# VoltageRegulator.net
KiCad netlist of a schematic drawn in Altium Designer
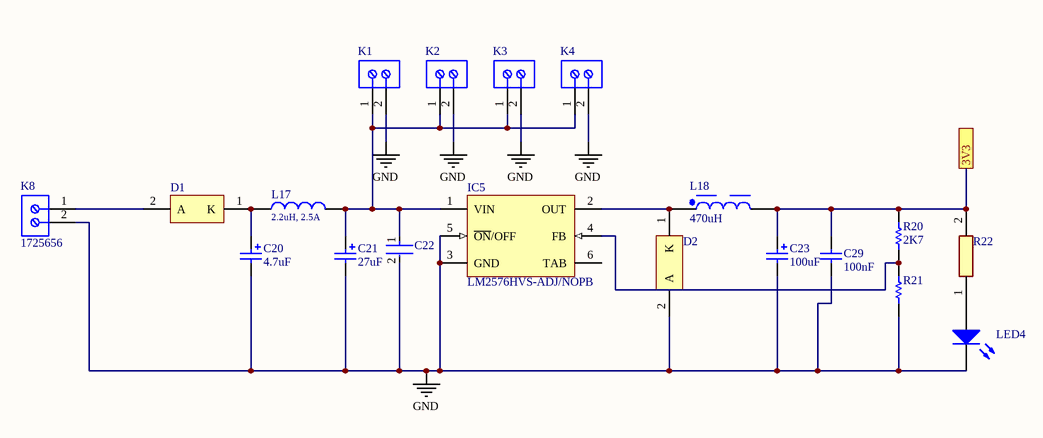
[diagram p0: VoltageRegulator.SchDoc]

(export (version "E")
  (design (tool "Eeschema 10.0.6"))
  (components
    (comp (ref "C20")
      (value "4.7uF")
      (footprint "WCAP-PSLP_D6.3H7.7")
      (description "WCAP-PSLP Aluminum Polymer Capacitor, V-Chip, SMT, D6.3xH7.7mm, 4.7uF, 100V")
      (fields
        (field (name "MANUFACTURER PART NUMBER") "875105945001")
        (field (name "MANUFACTURER") "Wurth Elektronik")
      )
      (libsource (lib "Altium_WCAP-PSLP (rev20b)") (part "875105945001"))
    )
    (comp (ref "C21")
      (value "27uF")
      (footprint "WCAP-ATUL_D8H11.5")
      (description "WCAP-ATUL Aluminum Electrolytic Capacitor, Radial, THT, D8xH11.5mm, 27uF, 100V")
      (fields
        (field (name "MANUFACTURER") "Wurth Elektronik")
        (field (name "MANUFACTURER PART NUMBER") "860040874001")
      )
      (libsource (lib "Altium_WCAP-ATUL (rev20b)") (part "860040874001"))
    )
    (comp (ref "C22")
      (value "~")
      (footprint "FP-GRM32-MFG")
      (description "CAP CER 4.7UF 50V X7R 1210")
      (fields (field (name "MANUFACTURER") "Murata") (field (name "TOLERANCE") "10%"))
      (libsource (lib "Altium Content Vault") (part "b4654b650e69147ec39a6b967a45e02"))
    )
    (comp (ref "C23")
      (value "100uF")
      (footprint "WCAP-PSLP_D5H5.5")
      (description "WCAP-PSLP Aluminum Polymer Capacitor, V-Chip, SMT, D5xH5.5mm, 100uF, 10V")
      (fields
        (field (name "MANUFACTURER PART NUMBER") "875105242010")
        (field (name "MANUFACTURER") "Wurth Elektronik")
      )
      (libsource (lib "Altium_WCAP-PSLP (rev20b)") (part "875105242010"))
    )
    (comp (ref "C29")
      (value "100nF")
      (footprint "WCAP-CSGP_0805_H=1.25mm")
      (description "WCAP-CSGP Multilayer Ceramic Chip Capacitor, General Purpose, size 0805, X7R, 100nF, 100V")
      (fields
        (field (name "MANUFACTURER PART NUMBER") "885012207128")
        (field (name "MANUFACTURER") "Wurth Elektronik")
      )
      (libsource (lib "Altium_WCAP-CSGP (rev21a)") (part "885012207128"))
    )
    (comp (ref "D1")
      (value "~")
      (footprint "ONSC-SMC-2-403-03_V")
      (description "Schottky Power Rectifier, 2-Pin SMC, Pb-Free, Tape and Reel")
      (fields (field (name "MANUFACTURER") "On Semiconductor") (field (name "PARTNUMBER") "MBRS540T3G"))
      (libsource (lib "Altium Content Vault") (part "ONSC-D-K1A2-2_A"))
    )
    (comp (ref "D2")
      (value "~")
      (footprint "ONSC-SMC-2-403-03_V")
      (description "Schottky Power Rectifier, 2-Pin SMC, Pb-Free, Tape and Reel")
      (fields (field (name "MANUFACTURER") "On Semiconductor") (field (name "PARTNUMBER") "MBRS540T3G"))
      (libsource (lib "") (part "ONSC-D-K1A2-2_A_1"))
    )
    (comp (ref "IC5")
      (value "LM2576HVS-ADJ/NOPB")
      (footprint "KTT0005B_N")
      (description "SIMPLE SWITCHER® 3A Step-Down Voltage Regulator, 5-pin TO-263, Pb-Free")
      (fields (field (name "MANUFACTURER") "Texas Instruments"))
      (libsource (lib "Altium Content Vault") (part "PM-REG-LM2575HVS-12"))
    )
    (comp (ref "K1")
      (value "~")
      (footprint "PHOE-1725656-2")
      (description "Male Header, Pitch 2.54 mm, 1 x 2 Position, Height 9 mm, Tail Length 3.5 mm")
      (fields
        (field (name "MANUFACTURER PART NO.") "1725656")
        (field (name "MANUFACTURER") "Phoenix Contact")
      )
      (libsource (lib "Altium Content Vault") (part "CN-1P-F-TB2"))
    )
    (comp (ref "K2")
      (value "~")
      (footprint "PHOE-1725656-2")
      (description "Male Header, Pitch 2.54 mm, 1 x 2 Position, Height 9 mm, Tail Length 3.5 mm")
      (fields
        (field (name "MANUFACTURER PART NO.") "1725656")
        (field (name "MANUFACTURER") "Phoenix Contact")
      )
      (libsource (lib "Altium Content Vault") (part "CN-1P-F-TB2"))
    )
    (comp (ref "K3")
      (value "~")
      (footprint "PHOE-1725656-2")
      (description "Male Header, Pitch 2.54 mm, 1 x 2 Position, Height 9 mm, Tail Length 3.5 mm")
      (fields
        (field (name "MANUFACTURER PART NO.") "1725656")
        (field (name "MANUFACTURER") "Phoenix Contact")
      )
      (libsource (lib "Altium Content Vault") (part "CN-1P-F-TB2"))
    )
    (comp (ref "K4")
      (value "~")
      (footprint "PHOE-1725656-2")
      (description "Male Header, Pitch 2.54 mm, 1 x 2 Position, Height 9 mm, Tail Length 3.5 mm")
      (fields
        (field (name "MANUFACTURER PART NO.") "1725656")
        (field (name "MANUFACTURER") "Phoenix Contact")
      )
      (libsource (lib "Altium Content Vault") (part "CN-1P-F-TB2"))
    )
    (comp (ref "K8")
      (value "1725656")
      (footprint "PHOE-1725656-2")
      (description "Male Header, Pitch 2.54 mm, 1 x 2 Position, Height 9 mm, Tail Length 3.5 mm")
      (fields (field (name "MANUFACTURER") "Phoenix Contact"))
      (libsource (lib "Altium Content Vault") (part "CN-1P-F-TB2"))
    )
    (comp (ref "L17")
      (value "2.2uH, 2.5A")
      (footprint "WE-PD2_4532")
      (description "WE-PD2 SMT Power Inductor, size 4532, 2.2uH, 2.5A")
      (fields
        (field (name "MANUFACTURER") "Wurth Elektronik")
        (field (name "MANUFACTURER PART NUMBER") "744773022")
      )
      (libsource (lib "WE-PD2 (rev20a)") (part "744773022"))
    )
    (comp (ref "L18")
      (value "470uH")
      (footprint "WE-PD_1050P")
      (description "WE-PD SMT Power Inductor, size 1050P, 470uH, 0.6A, 960mOhm")
      (fields
        (field (name "MANUFACTURER") "Wurth Elektronik")
        (field (name "MANUFACTURER PART NUMBER") "7447714471")
      )
      (libsource (lib "WE-PD (rev20b)") (part "7447714471"))
    )
    (comp (ref "LED4")
      (value "~")
      (footprint "Type 3mm")
      (description "THT LED round mono-color waterclear, WL-TMRW , Blue")
      (fields (field (name "MANUFACTURER") "Wuerth Elektronik") (field (name "PARTNUMBER") "151033BS03000"))
      (libsource (lib "Altium Content Vault") (part "WE-LED_K1A2-2"))
    )
    (comp (ref "R20")
      (value "2K7")
      (footprint "RESC2013X70X40ML20T20")
      (fields (field (name "PART NUMBER") "ERJ-6GEYJ272V") (field (name "MANUFACTURER") "Panasonic"))
      (libsource (lib "Altium Content Vault") (part "RES"))
    )
    (comp (ref "R21")
      (value "~")
      (footprint "RESC2013X70X40NL20T20")
      (fields (field (name "MANUFACTURER") "Panasonic") (field (name "PART NUMBER") "ERJ6ENF1601V"))
      (libsource (lib "Altium Content Vault") (part "RES"))
    )
    (comp (ref "R22")
      (value "~")
      (footprint "SamacSys:RESC1608X55N")
      (description "Resistor")
      (fields
        (field (name "MANUFACTURER_PART_NUMBER") "RC0603JR-071KL")
        (field (name "MOUSER PART NUMBER") "603-RC0603JR-071KL")
      )
      (libsource (lib "SamacSys") (part "RC0603JR-071KL"))
    )
  )
  (nets
    (net (code "1") (name "/3V3") (class "Default")
      (node (ref "C23") (pin "1") (pinfunction "P_1") (pintype "passive"))
      (node (ref "C29") (pin "2") (pinfunction "2_2") (pintype "passive"))
      (node (ref "L18") (pin "2") (pinfunction "2_2") (pintype "passive"))
      (node (ref "R20") (pin "2") (pinfunction "2_2") (pintype "passive"))
      (node (ref "R22") (pin "2") (pinfunction "2_2") (pintype "passive"))
    )
    (net (code "2") (name "GND") (class "Default")
      (node (ref "C20") (pin "2") (pinfunction "N_2") (pintype "passive"))
      (node (ref "C21") (pin "2") (pinfunction "N_2") (pintype "passive"))
      (node (ref "C22") (pin "2") (pinfunction "2_2") (pintype "passive"))
      (node (ref "C23") (pin "2") (pinfunction "N_2") (pintype "passive"))
      (node (ref "C29") (pin "1") (pinfunction "1_1") (pintype "passive"))
      (node (ref "D2") (pin "2") (pinfunction "A_2") (pintype "passive"))
      (node (ref "IC5") (pin "3") (pinfunction "GND_3") (pintype "power_in"))
      (node (ref "IC5") (pin "5") (pinfunction "~{ON}/OFF_5") (pintype "input"))
      (node (ref "K1") (pin "2") (pinfunction "2_2") (pintype "passive"))
      (node (ref "K2") (pin "2") (pinfunction "2_2") (pintype "passive"))
      (node (ref "K3") (pin "2") (pinfunction "2_2") (pintype "passive"))
      (node (ref "K4") (pin "2") (pinfunction "2_2") (pintype "passive"))
      (node (ref "K8") (pin "2") (pinfunction "2_2") (pintype "passive"))
      (node (ref "LED4") (pin "1") (pinfunction "K_1") (pintype "passive"))
      (node (ref "R21") (pin "1") (pinfunction "1_1") (pintype "passive"))
    )
    (net (code "3") (name "Net-(C20-P)") (class "Default")
      (node (ref "C20") (pin "1") (pinfunction "P_1") (pintype "passive"))
      (node (ref "D1") (pin "1") (pinfunction "K_1") (pintype "passive"))
      (node (ref "L17") (pin "1") (pinfunction "1_1") (pintype "passive"))
    )
    (net (code "4") (name "Net-(C21-P)") (class "Default")
      (node (ref "C21") (pin "1") (pinfunction "P_1") (pintype "passive"))
      (node (ref "C22") (pin "1") (pinfunction "1_1") (pintype "passive"))
      (node (ref "IC5") (pin "1") (pinfunction "VIN_1") (pintype "power_in"))
      (node (ref "K1") (pin "1") (pinfunction "1_1") (pintype "passive"))
      (node (ref "K2") (pin "1") (pinfunction "1_1") (pintype "passive"))
      (node (ref "K3") (pin "1") (pinfunction "1_1") (pintype "passive"))
      (node (ref "K4") (pin "1") (pinfunction "1_1") (pintype "passive"))
      (node (ref "L17") (pin "2") (pinfunction "2_2") (pintype "passive"))
    )
    (net (code "5") (name "Net-(D1-A)") (class "Default")
      (node (ref "D1") (pin "2") (pinfunction "A_2") (pintype "passive"))
      (node (ref "K8") (pin "1") (pinfunction "1_1") (pintype "passive"))
    )
    (net (code "6") (name "Net-(D2-K)") (class "Default")
      (node (ref "D2") (pin "1") (pinfunction "K_1") (pintype "passive"))
      (node (ref "IC5") (pin "2") (pinfunction "OUT_2") (pintype "power_in"))
      (node (ref "L18") (pin "1") (pinfunction "1_1") (pintype "passive"))
    )
    (net (code "7") (name "Net-(IC5-FB)") (class "Default")
      (node (ref "IC5") (pin "4") (pinfunction "FB_4") (pintype "input"))
      (node (ref "R20") (pin "1") (pinfunction "1_1") (pintype "passive"))
      (node (ref "R21") (pin "2") (pinfunction "2_2") (pintype "passive"))
    )
    (net (code "8") (name "Net-(LED4-A)") (class "Default")
      (node (ref "LED4") (pin "2") (pinfunction "A_2") (pintype "passive"))
      (node (ref "R22") (pin "1") (pinfunction "1_1") (pintype "passive"))
    )
    (net (code "9") (name "unconnected-(IC5-TAB-Pad6)") (class "Default")
      (node (ref "IC5") (pin "6") (pinfunction "TAB_6") (pintype "power_in"))
    )
  )
)
